# 4_SD_Card_NFC.net
KiCad netlist of a schematic drawn in Altium Designer
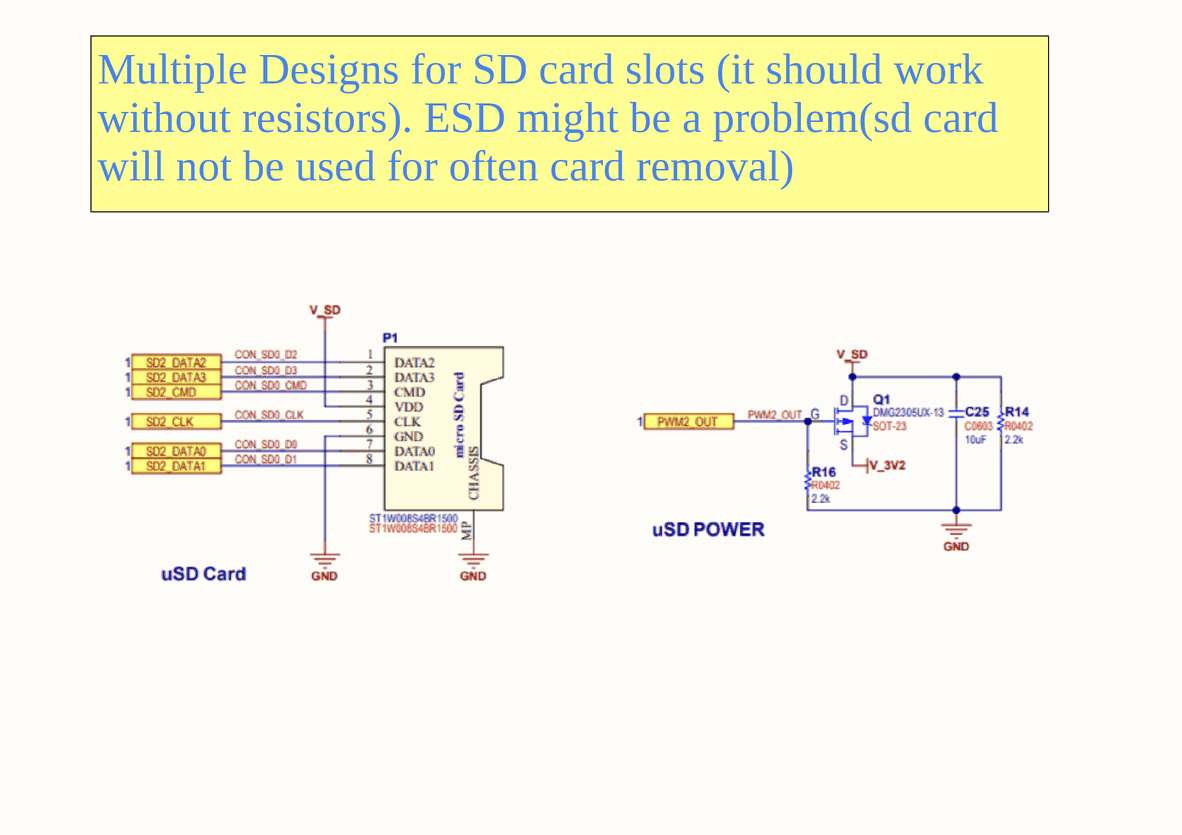
[diagram p0: 4_SD_Card_NFC.SchDoc, top middle]
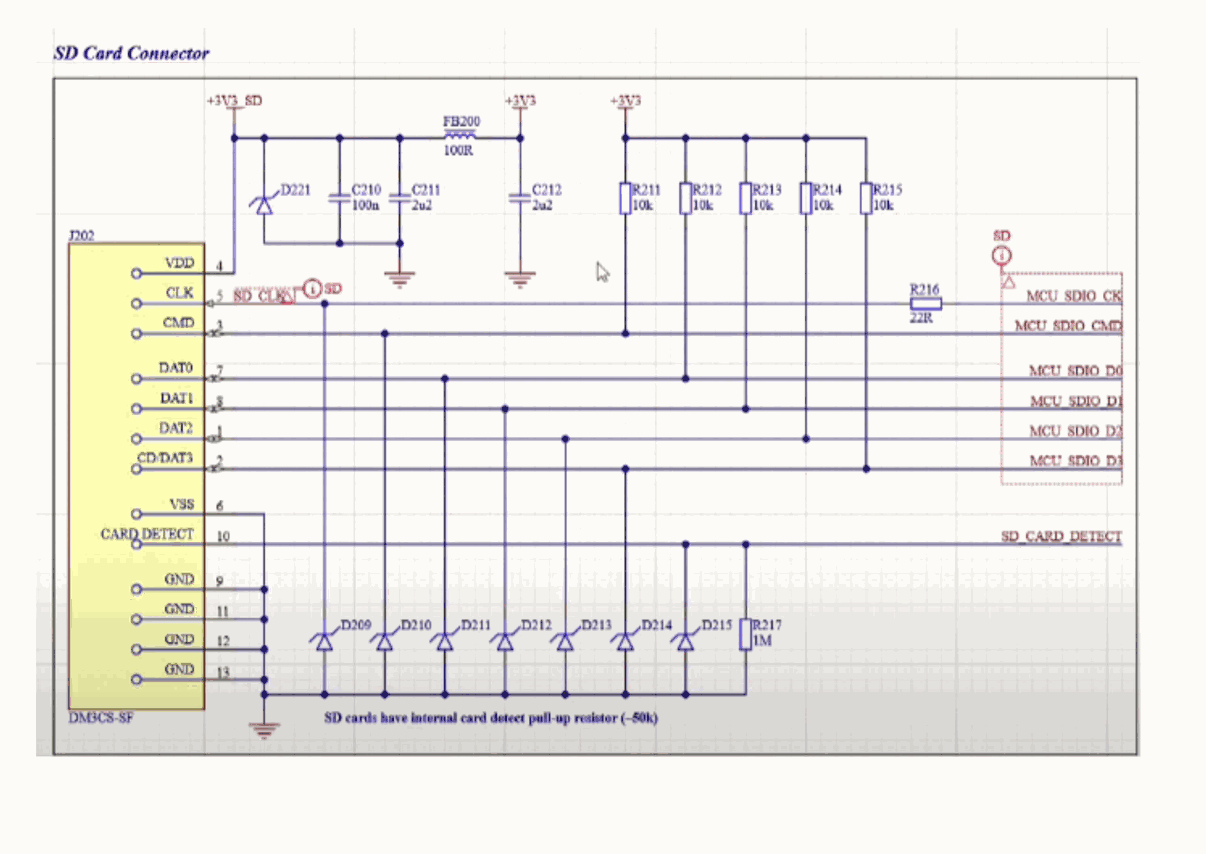
[diagram p1: 4_SD_Card_NFC.SchDoc, bottom left]
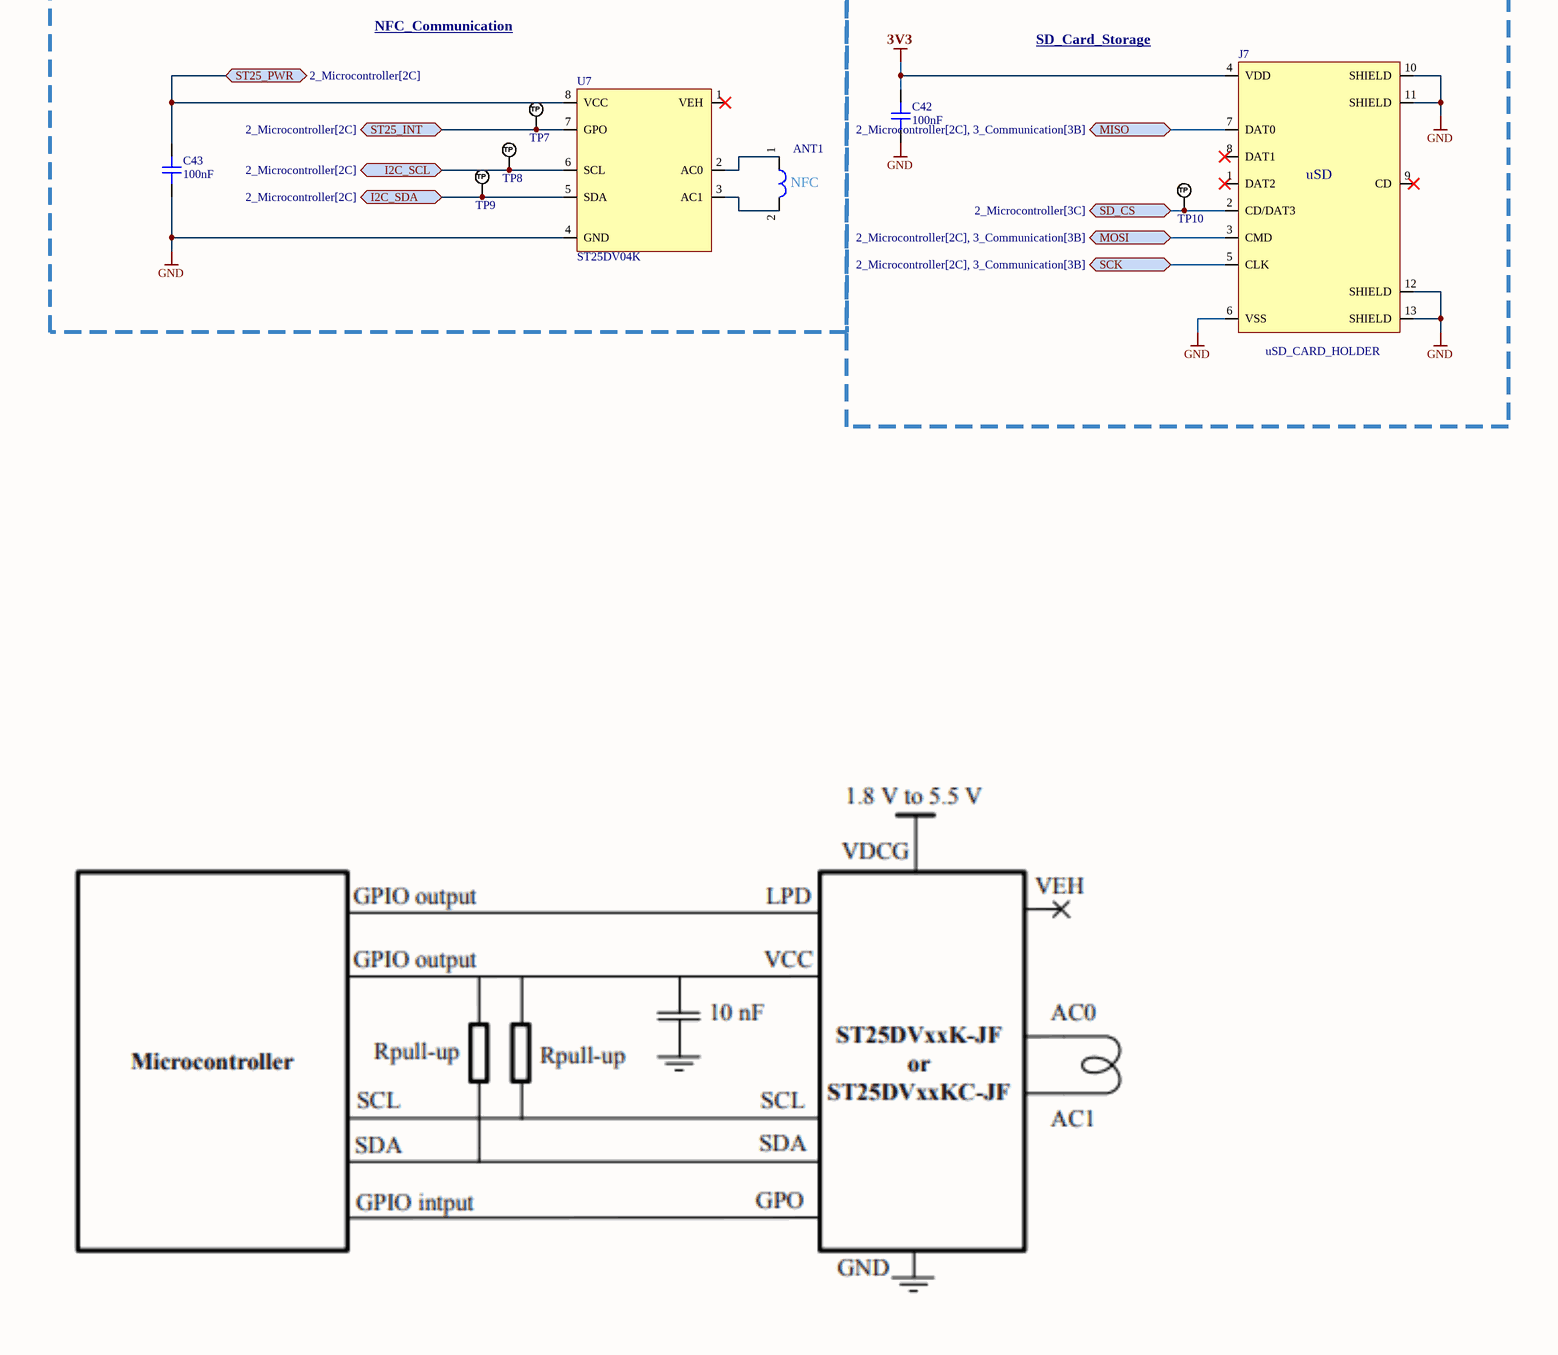
[diagram p2: 4_SD_Card_NFC.SchDoc, bottom middle]
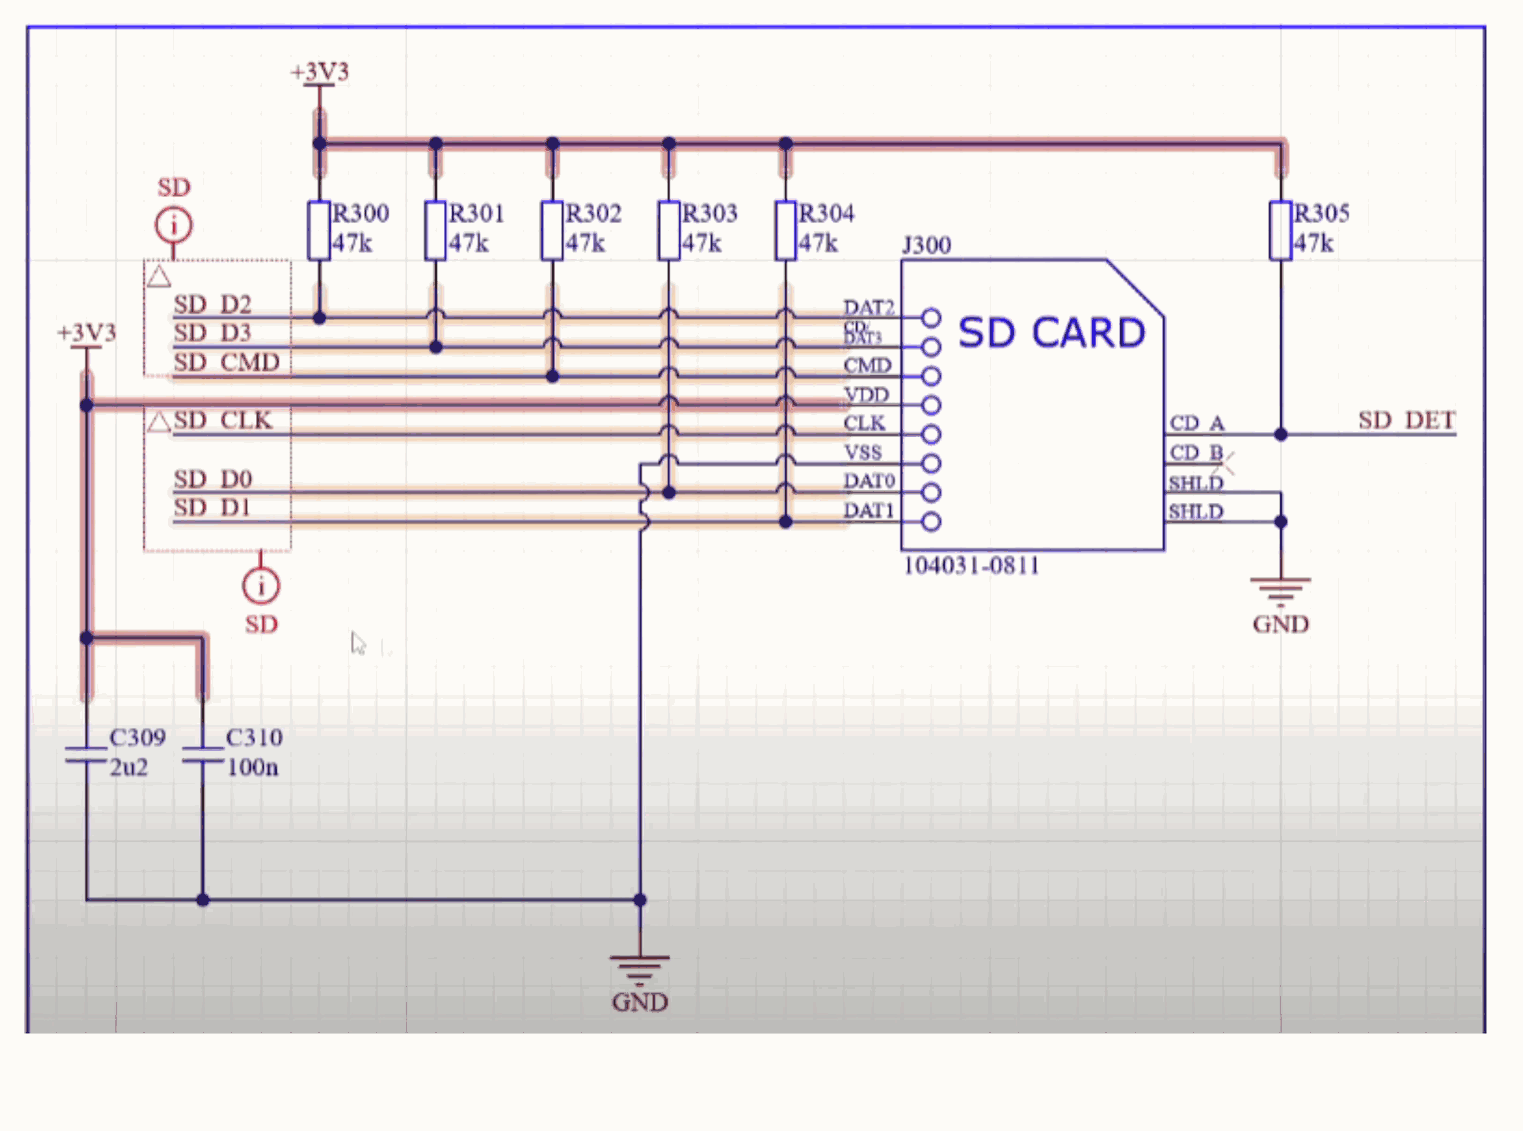
[diagram p3: 4_SD_Card_NFC.SchDoc, bottom right]

(export (version "E")
  (design (tool "Eeschema 10.0.6"))
  (components
    (comp (ref "ANT1")
      (value "NFC_ANTENNA")
      (footprint "ANT16")
      (libsource (lib "Schlib1") (part "NFC_ANTENNA"))
    )
    (comp (ref "C42")
      (value "100nF")
      (footprint "C0603")
      (description "Capacitor SMD 0603")
      (libsource (lib "Schlib_H2") (part "CAP_0603"))
    )
    (comp (ref "C43")
      (value "100nF")
      (footprint "C0603")
      (description "Capacitor SMD 0603")
      (libsource (lib "Schlib1") (part "CAP_0603"))
    )
    (comp (ref "J7")
      (value "uSD_CARD_HOLDER")
      (footprint "TF115BCP9")
      (libsource (lib "Schlib_H2") (part "uSD_CARD"))
    )
    (comp (ref "TP7")
      (value "TP_NOBOM")
      (footprint "TEST_PAD_THD")
      (description "Test Point Round 1mm (NO BOM)")
      (libsource (lib "Schlib_H2") (part "TEST_POINT_RND_1MM"))
    )
    (comp (ref "TP8")
      (value "TP_NOBOM")
      (footprint "TEST_PAD_THD")
      (description "Test Point Round 1mm (NO BOM)")
      (libsource (lib "Schlib_H2") (part "TEST_POINT_RND_1MM"))
    )
    (comp (ref "TP9")
      (value "TP_NOBOM")
      (footprint "TEST_PAD_THD")
      (description "Test Point Round 1mm (NO BOM)")
      (libsource (lib "Schlib_H2") (part "TEST_POINT_RND_1MM"))
    )
    (comp (ref "TP10")
      (value "TP_NOBOM")
      (footprint "TEST_PAD_THD")
      (description "Test Point Round 1mm (NO BOM)")
      (libsource (lib "Schlib_H2") (part "TEST_POINT_RND_1MM"))
    )
    (comp (ref "U7")
      (value "ST25DV04K")
      (footprint "SOIC-SN8_N")
      (description "ST25DO4K NFC module with I2C")
      (libsource (lib "Schlib1") (part "ST25DV04K"))
    )
  )
  (nets
    (net (code "1") (name "/I2C_SCL") (class "Default")
      (node (ref "TP8") (pin "1") (pinfunction "TP_1") (pintype "passive"))
      (node (ref "U7") (pin "6") (pinfunction "SCL_6") (pintype "passive"))
    )
    (net (code "2") (name "/I2C_SDA") (class "Default")
      (node (ref "TP9") (pin "1") (pinfunction "TP_1") (pintype "passive"))
      (node (ref "U7") (pin "5") (pinfunction "SDA_5") (pintype "passive"))
    )
    (net (code "3") (name "/MISO") (class "Default")
      (node (ref "J7") (pin "7") (pinfunction "DAT0_7") (pintype "passive"))
    )
    (net (code "4") (name "/MOSI") (class "Default")
      (node (ref "J7") (pin "3") (pinfunction "CMD_3") (pintype "passive"))
    )
    (net (code "5") (name "/SCK") (class "Default")
      (node (ref "J7") (pin "5") (pinfunction "CLK_5") (pintype "passive"))
    )
    (net (code "6") (name "/SD_CS") (class "Default")
      (node (ref "J7") (pin "2") (pinfunction "CD/DAT3_2") (pintype "passive"))
      (node (ref "TP10") (pin "1") (pinfunction "TP_1") (pintype "passive"))
    )
    (net (code "7") (name "/ST25_INT") (class "Default")
      (node (ref "TP7") (pin "1") (pinfunction "TP_1") (pintype "passive"))
      (node (ref "U7") (pin "7") (pinfunction "GPO_7") (pintype "passive"))
    )
    (net (code "8") (name "/ST25_PWR") (class "Default")
      (node (ref "C43") (pin "2") (pinfunction "2_2") (pintype "passive"))
      (node (ref "U7") (pin "8") (pinfunction "VCC_8") (pintype "passive"))
    )
    (net (code "9") (name "3V3") (class "Default")
      (node (ref "C42") (pin "2") (pinfunction "2_2") (pintype "passive"))
      (node (ref "J7") (pin "4") (pinfunction "VDD_4") (pintype "passive"))
    )
    (net (code "10") (name "GND") (class "Default")
      (node (ref "C42") (pin "1") (pinfunction "1_1") (pintype "passive"))
      (node (ref "C43") (pin "1") (pinfunction "1_1") (pintype "passive"))
      (node (ref "J7") (pin "10") (pinfunction "SHIELD_10") (pintype "passive"))
      (node (ref "J7") (pin "11") (pinfunction "SHIELD_11") (pintype "passive"))
      (node (ref "J7") (pin "12") (pinfunction "SHIELD_12") (pintype "passive"))
      (node (ref "J7") (pin "13") (pinfunction "SHIELD_13") (pintype "passive"))
      (node (ref "J7") (pin "6") (pinfunction "VSS_6") (pintype "passive"))
      (node (ref "U7") (pin "4") (pinfunction "GND_4") (pintype "passive"))
    )
    (net (code "11") (name "Net-(U7-AC0)") (class "Default")
      (node (ref "ANT1") (pin "1") (pinfunction "1_1") (pintype "passive"))
      (node (ref "U7") (pin "2") (pinfunction "AC0_2") (pintype "passive"))
    )
    (net (code "12") (name "Net-(U7-AC1)") (class "Default")
      (node (ref "ANT1") (pin "2") (pinfunction "2_2") (pintype "passive"))
      (node (ref "U7") (pin "3") (pinfunction "AC1_3") (pintype "passive"))
    )
    (net (code "13") (name "unconnected-(J7-CD-Pad9)") (class "Default")
      (node (ref "J7") (pin "9") (pinfunction "CD_9") (pintype "passive+no_connect"))
    )
    (net (code "14") (name "unconnected-(J7-DAT1-Pad8)") (class "Default")
      (node (ref "J7") (pin "8") (pinfunction "DAT1_8") (pintype "passive+no_connect"))
    )
    (net (code "15") (name "unconnected-(J7-DAT2-Pad1)") (class "Default")
      (node (ref "J7") (pin "1") (pinfunction "DAT2_1") (pintype "passive+no_connect"))
    )
    (net (code "16") (name "unconnected-(U7-VEH-Pad1)") (class "Default")
      (node (ref "U7") (pin "1") (pinfunction "VEH_1") (pintype "passive+no_connect"))
    )
  )
)
